# feather-v2_0.net
KiCad netlist of a schematic drawn in EAGLE
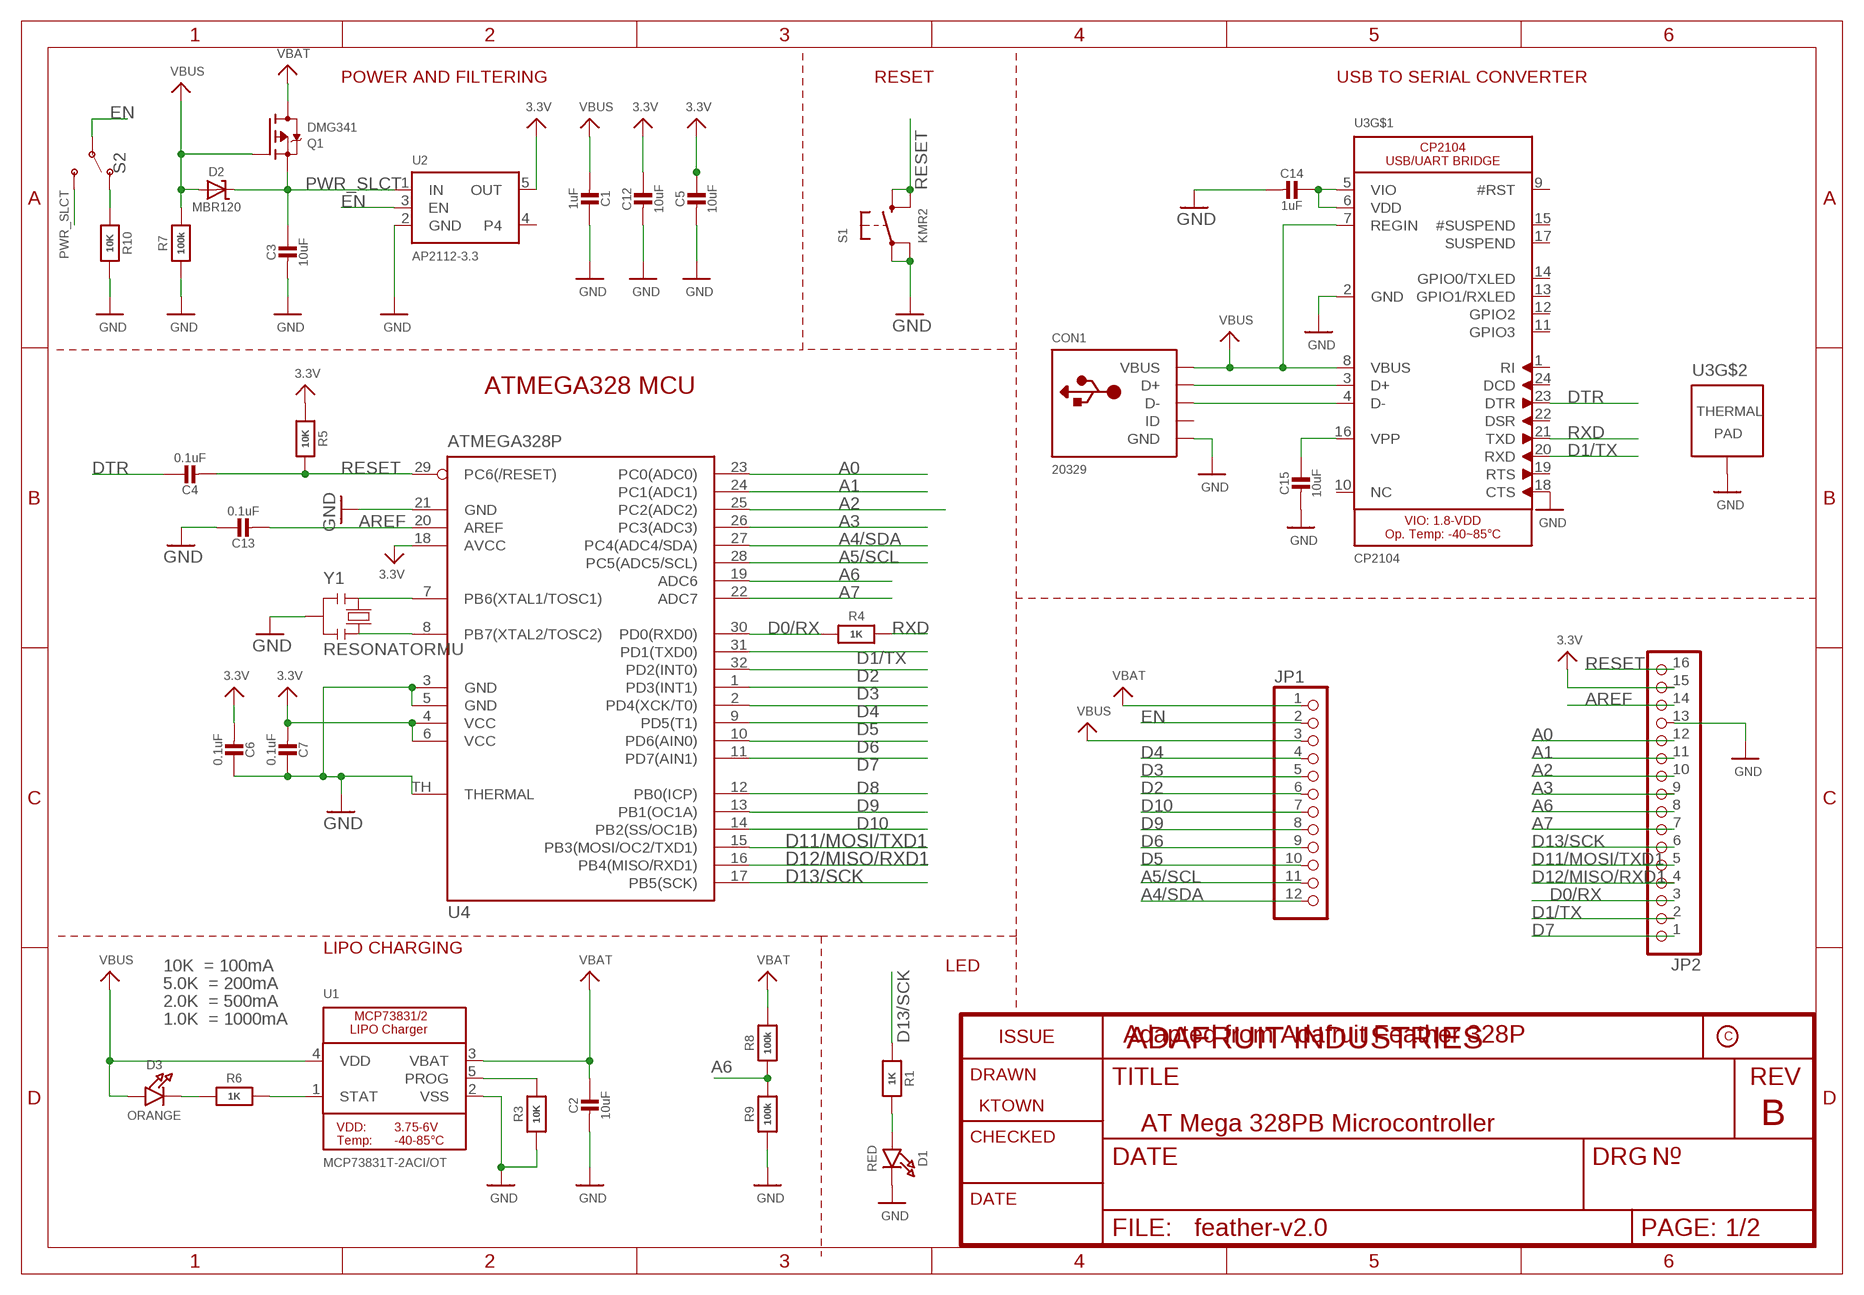
[diagram p0: schematic, sheet 1]
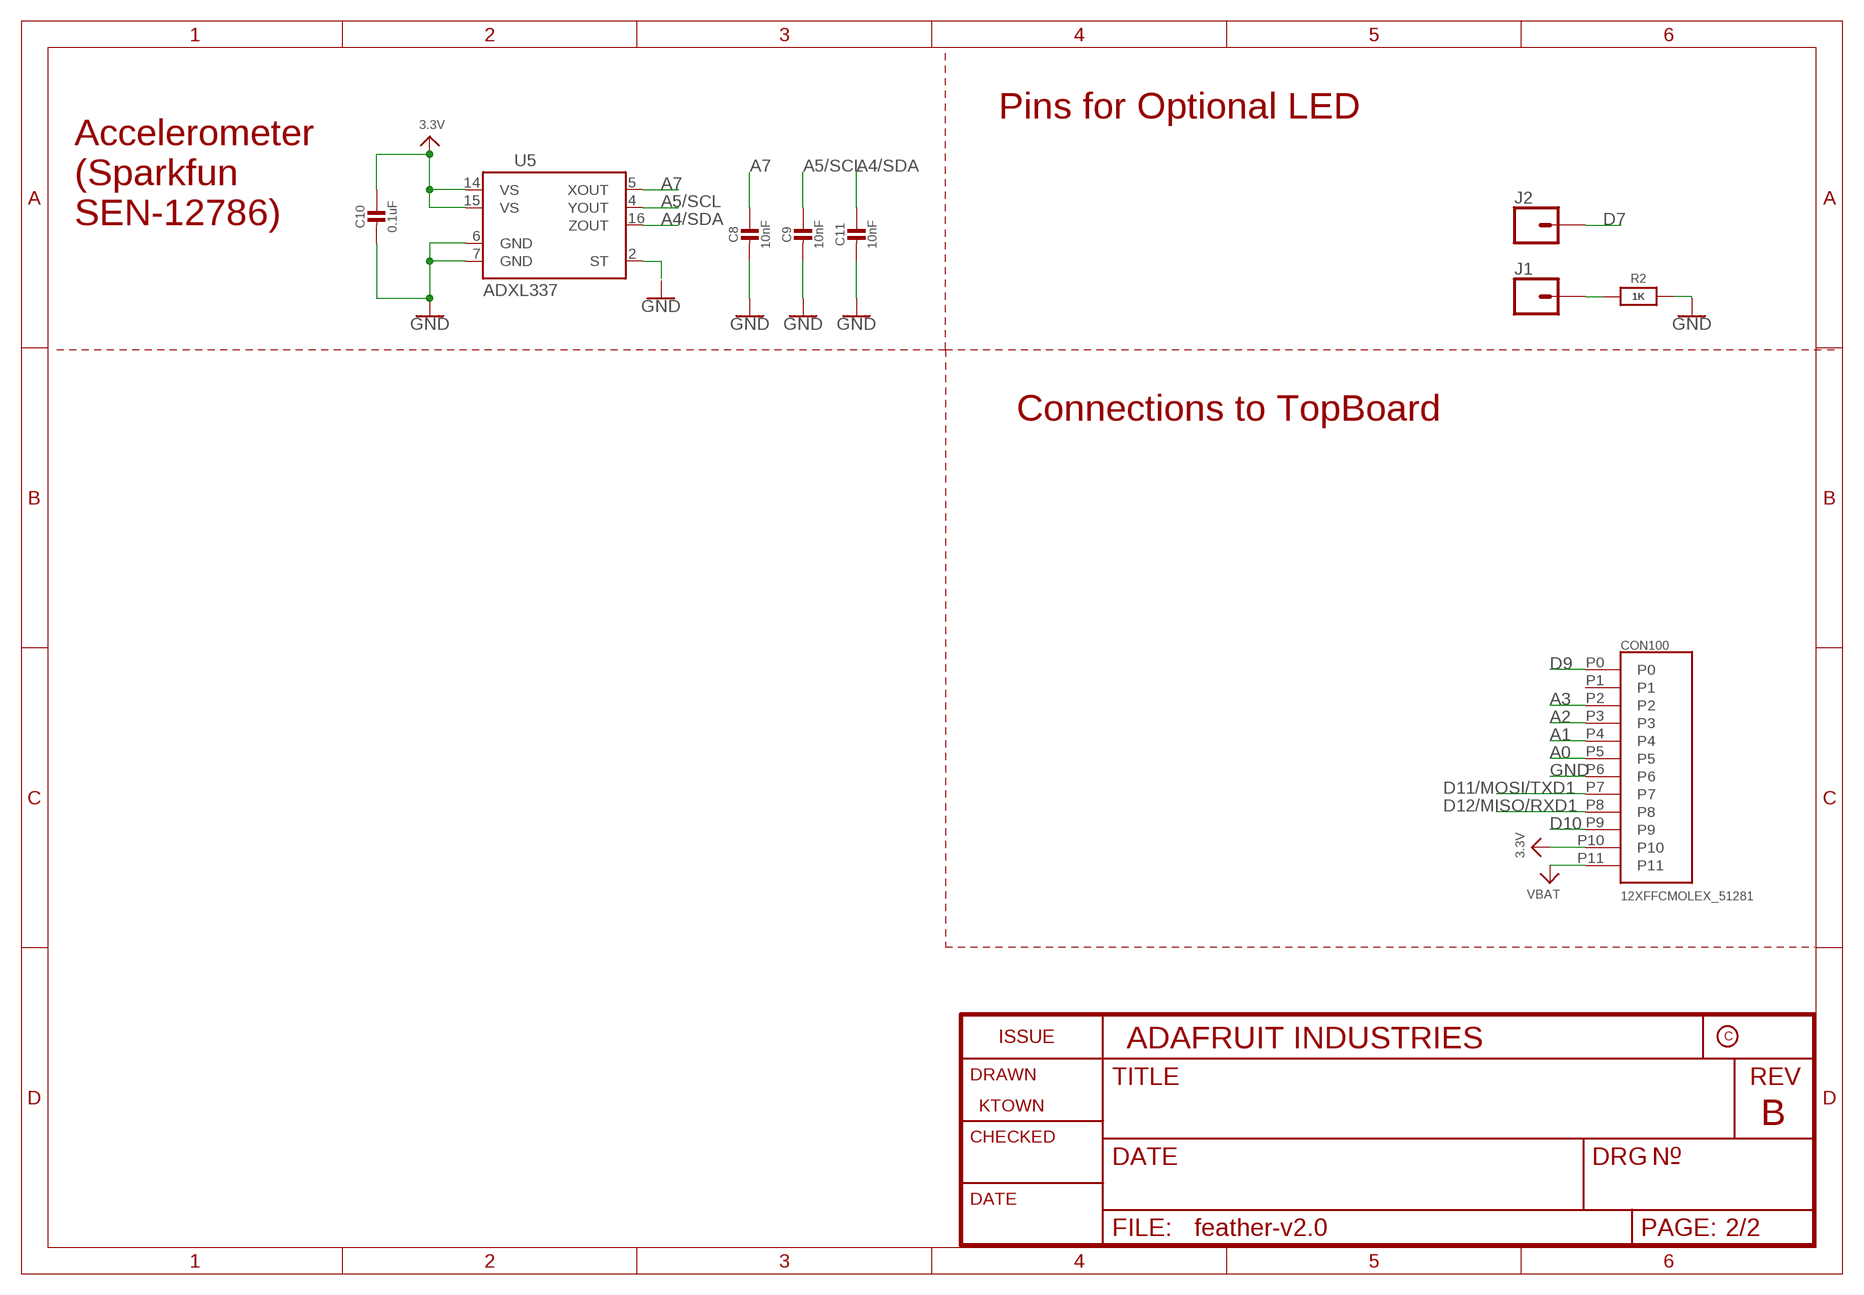
[diagram p1: schematic, sheet 2]

(export (version "E")
  (design (tool "Eeschema 10.0.6"))
  (components
    (comp (ref "C8")
      (value "10nF")
      (footprint "eagle-import:_0603MP")
      (libsource (lib "eagle-import") (part "CAP_CERAMIC_0603MP"))
    )
    (comp (ref "C9")
      (value "10nF")
      (footprint "eagle-import:_0603MP")
      (libsource (lib "eagle-import") (part "CAP_CERAMIC_0603MP"))
    )
    (comp (ref "C10")
      (value "0.1uF")
      (footprint "eagle-import:_0603MP")
      (libsource (lib "eagle-import") (part "CAP_CERAMIC_0603MP"))
    )
    (comp (ref "C11")
      (value "10nF")
      (footprint "eagle-import:_0603MP")
      (libsource (lib "eagle-import") (part "CAP_CERAMIC_0603MP"))
    )
    (comp (ref "CON100")
      (value "12XFFCMOLEX_51281")
      (footprint "eagle-import:MOLEX_51281-1294")
      (libsource (lib "eagle-import") (part "12XFFCMOLEX_51281"))
    )
    (comp (ref "J1")
      (value "CONN_01PTH_NO_SILK_YES_STOP")
      (footprint "eagle-import:1X01_NO_SILK")
      (libsource (lib "eagle-import") (part "CONN_01PTH_NO_SILK_YES_STOP"))
    )
    (comp (ref "J2")
      (value "CONN_01PTH_NO_SILK_YES_STOP")
      (footprint "eagle-import:1X01_NO_SILK")
      (libsource (lib "eagle-import") (part "CONN_01PTH_NO_SILK_YES_STOP"))
    )
    (comp (ref "R2")
      (value "1K")
      (footprint "eagle-import:_0603MP")
      (libsource (lib "eagle-import") (part "RESISTOR_0603MP"))
    )
    (comp (ref "U5")
      (value "ADXL337")
      (footprint "eagle-import:LFCSP_LQ-16")
      (libsource (lib "eagle-import") (part "ADXL337"))
    )
    (comp (ref "C1")
      (value "1uF")
      (footprint "eagle-import:_0603MP")
      (libsource (lib "eagle-import") (part "CAP_CERAMIC_0603MP"))
    )
    (comp (ref "C2")
      (value "10uF")
      (footprint "eagle-import:_0603MP")
      (libsource (lib "eagle-import") (part "CAP_CERAMIC_0603MP"))
    )
    (comp (ref "C3")
      (value "10uF")
      (footprint "eagle-import:_0603MP")
      (libsource (lib "eagle-import") (part "CAP_CERAMIC_0603MP"))
    )
    (comp (ref "C4")
      (value "0.1uF")
      (footprint "eagle-import:_0603MP")
      (libsource (lib "eagle-import") (part "CAP_CERAMIC_0603MP"))
    )
    (comp (ref "C5")
      (value "10uF")
      (footprint "eagle-import:_0603MP")
      (libsource (lib "eagle-import") (part "CAP_CERAMIC_0603MP"))
    )
    (comp (ref "C6")
      (value "0.1uF")
      (footprint "eagle-import:_0603MP")
      (libsource (lib "eagle-import") (part "CAP_CERAMIC_0603MP"))
    )
    (comp (ref "C7")
      (value "0.1uF")
      (footprint "eagle-import:_0603MP")
      (libsource (lib "eagle-import") (part "CAP_CERAMIC_0603MP"))
    )
    (comp (ref "C12")
      (value "10uF")
      (footprint "eagle-import:_0603MP")
      (libsource (lib "eagle-import") (part "CAP_CERAMIC_0603MP"))
    )
    (comp (ref "C13")
      (value "0.1uF")
      (footprint "eagle-import:_0603MP")
      (libsource (lib "eagle-import") (part "CAP_CERAMIC_0603MP"))
    )
    (comp (ref "C14")
      (value "1uF")
      (footprint "eagle-import:_0603MP")
      (libsource (lib "eagle-import") (part "CAP_CERAMIC_0603MP"))
    )
    (comp (ref "C15")
      (value "10uF")
      (footprint "eagle-import:_0603MP")
      (libsource (lib "eagle-import") (part "CAP_CERAMIC_0603MP"))
    )
    (comp (ref "CON1")
      (value "20329")
      (footprint "eagle-import:4UCONN_20329_V2")
      (libsource (lib "eagle-import") (part "USB_MICRO_20329_V2"))
    )
    (comp (ref "D1")
      (value "RED")
      (footprint "eagle-import:CHIPLED_0603_NOOUTLINE")
      (libsource (lib "eagle-import") (part "LED0603_NOOUTLINE"))
    )
    (comp (ref "D2")
      (value "MBR120")
      (footprint "eagle-import:SOD-323")
      (libsource (lib "eagle-import") (part "DIODE-SCHOTTKYSOD-323"))
    )
    (comp (ref "D3")
      (value "ORANGE")
      (footprint "eagle-import:CHIPLED_0603_NOOUTLINE")
      (libsource (lib "eagle-import") (part "LED0603_NOOUTLINE"))
    )
    (comp (ref "JP1")
      (value "HEADER-1X12")
      (footprint "eagle-import:1X12_ROUND")
      (libsource (lib "eagle-import") (part "HEADER-1X12"))
    )
    (comp (ref "JP2")
      (value "HEADER-1X16ROUND")
      (footprint "eagle-import:1X16_ROUND")
      (libsource (lib "eagle-import") (part "HEADER-1X16ROUND"))
    )
    (comp (ref "Q1")
      (value "DMG341")
      (footprint "eagle-import:SOT23-R")
      (libsource (lib "eagle-import") (part "MOSFET-P"))
    )
    (comp (ref "R1")
      (value "1K")
      (footprint "eagle-import:_0603MP")
      (libsource (lib "eagle-import") (part "RESISTOR_0603MP"))
    )
    (comp (ref "R3")
      (value "10K")
      (footprint "eagle-import:_0603MP")
      (libsource (lib "eagle-import") (part "RESISTOR_0603MP"))
    )
    (comp (ref "R4")
      (value "1K")
      (footprint "eagle-import:_0603MP")
      (libsource (lib "eagle-import") (part "RESISTOR_0603MP"))
    )
    (comp (ref "R5")
      (value "10K")
      (footprint "eagle-import:_0603MP")
      (libsource (lib "eagle-import") (part "RESISTOR_0603MP"))
    )
    (comp (ref "R6")
      (value "1K")
      (footprint "eagle-import:_0603MP")
      (libsource (lib "eagle-import") (part "RESISTOR_0603MP"))
    )
    (comp (ref "R7")
      (value "100k")
      (footprint "eagle-import:_0603MP")
      (libsource (lib "eagle-import") (part "RESISTOR_0603MP"))
    )
    (comp (ref "R8")
      (value "100k")
      (footprint "eagle-import:_0603MP")
      (libsource (lib "eagle-import") (part "RESISTOR_0603MP"))
    )
    (comp (ref "R9")
      (value "100k")
      (footprint "eagle-import:_0603MP")
      (libsource (lib "eagle-import") (part "RESISTOR_0603MP"))
    )
    (comp (ref "R10")
      (value "10K")
      (footprint "eagle-import:_0603MP")
      (libsource (lib "eagle-import") (part "RESISTOR_0603MP"))
    )
    (comp (ref "S1")
      (value "KMR2")
      (footprint "eagle-import:BTN_KMR2_4.6X2.8")
      (libsource (lib "eagle-import") (part "SWITCH_TACT_SMT4.6X2.8"))
    )
    (comp (ref "S2")
      (value "SWITCH-SPDT-SMD-RIGHT-ANGLE")
      (footprint "eagle-import:SWITCH_SPST_SMD_A")
      (libsource (lib "eagle-import") (part "SWITCH-SPDT-SMD-RIGHT-ANGLE"))
    )
    (comp (ref "U1")
      (value "MCP73831T-2ACI/OT")
      (footprint "eagle-import:SOT23-5")
      (libsource (lib "eagle-import") (part "MCP73831/2"))
    )
    (comp (ref "U2")
      (value "AP2112-3.3")
      (footprint "eagle-import:SOT23-5")
      (libsource (lib "eagle-import") (part "VREG_SOT23-5"))
    )
    (comp (ref "U3")
      (value "CP2104")
      (footprint "eagle-import:QFN24_4MM_SMSC")
      (libsource (lib "eagle-import") (part "CP2104"))
    )
    (comp (ref "U4")
      (value "ATMEGA328P")
      (footprint "eagle-import:MLF32-TH")
      (fields (field (name "MF") "MicroChip") (field (name "MPN") "ATMEGA328PB-MU"))
      (libsource (lib "eagle-import") (part "MEGA328PB"))
    )
    (comp (ref "Y1")
      (value "RESONATORMU")
      (footprint "eagle-import:RESONATOR")
      (libsource (lib "eagle-import") (part "RESONATORMU"))
    )
  )
  (nets
    (net (code "1") (name "3.3V") (class "Default")
      (node (ref "C10") (pin "1") (pinfunction "1_1") (pintype "passive"))
      (node (ref "C12") (pin "1") (pinfunction "1_1") (pintype "passive"))
      (node (ref "C5") (pin "1") (pinfunction "1_1") (pintype "passive"))
      (node (ref "C6") (pin "2") (pinfunction "2_2") (pintype "passive"))
      (node (ref "C7") (pin "2") (pinfunction "2_2") (pintype "passive"))
      (node (ref "CON100") (pin "P10") (pinfunction "P10_P10") (pintype "bidirectional"))
      (node (ref "JP2") (pin "15") (pinfunction "15_15") (pintype "passive"))
      (node (ref "R5") (pin "2") (pinfunction "2_2") (pintype "passive"))
      (node (ref "U2") (pin "5") (pinfunction "OUT_5") (pintype "power_in"))
      (node (ref "U4") (pin "18") (pinfunction "AVCC_18") (pintype "power_in"))
      (node (ref "U4") (pin "4") (pinfunction "VCC_4") (pintype "power_in"))
      (node (ref "U4") (pin "6") (pinfunction "VCC_6") (pintype "power_in"))
      (node (ref "U5") (pin "14") (pinfunction "VS_14") (pintype "bidirectional"))
      (node (ref "U5") (pin "15") (pinfunction "VS_15") (pintype "bidirectional"))
    )
    (net (code "2") (name "A0") (class "Default")
      (node (ref "CON100") (pin "P5") (pinfunction "P5_P5") (pintype "bidirectional"))
      (node (ref "JP2") (pin "12") (pinfunction "12_12") (pintype "passive"))
      (node (ref "U4") (pin "23") (pinfunction "PC0(ADC0)_23") (pintype "bidirectional"))
    )
    (net (code "3") (name "A1") (class "Default")
      (node (ref "CON100") (pin "P4") (pinfunction "P4_P4") (pintype "bidirectional"))
      (node (ref "JP2") (pin "11") (pinfunction "11_11") (pintype "passive"))
      (node (ref "U4") (pin "24") (pinfunction "PC1(ADC1)_24") (pintype "bidirectional"))
    )
    (net (code "4") (name "A2") (class "Default")
      (node (ref "CON100") (pin "P3") (pinfunction "P3_P3") (pintype "bidirectional"))
      (node (ref "JP2") (pin "10") (pinfunction "10_10") (pintype "passive"))
      (node (ref "U4") (pin "25") (pinfunction "PC2(ADC2)_25") (pintype "bidirectional"))
    )
    (net (code "5") (name "A3") (class "Default")
      (node (ref "CON100") (pin "P2") (pinfunction "P2_P2") (pintype "bidirectional"))
      (node (ref "JP2") (pin "9") (pinfunction "9_9") (pintype "passive"))
      (node (ref "U4") (pin "26") (pinfunction "PC3(ADC3)_26") (pintype "bidirectional"))
    )
    (net (code "6") (name "A4{slash}SDA") (class "Default")
      (node (ref "C11") (pin "1") (pinfunction "1_1") (pintype "passive"))
      (node (ref "JP1") (pin "12") (pinfunction "12_12") (pintype "passive"))
      (node (ref "U4") (pin "27") (pinfunction "PC4(ADC4/SDA)_27") (pintype "bidirectional"))
      (node (ref "U5") (pin "16") (pinfunction "ZOUT_16") (pintype "bidirectional"))
    )
    (net (code "7") (name "A5{slash}SCL") (class "Default")
      (node (ref "C9") (pin "1") (pinfunction "1_1") (pintype "passive"))
      (node (ref "JP1") (pin "11") (pinfunction "11_11") (pintype "passive"))
      (node (ref "U4") (pin "28") (pinfunction "PC5(ADC5/SCL)_28") (pintype "bidirectional"))
      (node (ref "U5") (pin "4") (pinfunction "YOUT_4") (pintype "bidirectional"))
    )
    (net (code "8") (name "A6") (class "Default")
      (node (ref "JP2") (pin "8") (pinfunction "8_8") (pintype "passive"))
      (node (ref "R8") (pin "1") (pinfunction "1_1") (pintype "passive"))
      (node (ref "R9") (pin "2") (pinfunction "2_2") (pintype "passive"))
      (node (ref "U4") (pin "19") (pinfunction "ADC6_19") (pintype "bidirectional"))
    )
    (net (code "9") (name "A7") (class "Default")
      (node (ref "C8") (pin "1") (pinfunction "1_1") (pintype "passive"))
      (node (ref "JP2") (pin "7") (pinfunction "7_7") (pintype "passive"))
      (node (ref "U4") (pin "22") (pinfunction "ADC7_22") (pintype "bidirectional"))
      (node (ref "U5") (pin "5") (pinfunction "XOUT_5") (pintype "bidirectional"))
    )
    (net (code "10") (name "AREF") (class "Default")
      (node (ref "C13") (pin "2") (pinfunction "2_2") (pintype "passive"))
      (node (ref "JP2") (pin "14") (pinfunction "14_14") (pintype "passive"))
      (node (ref "U4") (pin "20") (pinfunction "AREF_20") (pintype "passive"))
    )
    (net (code "11") (name "D0{slash}RX") (class "Default")
      (node (ref "JP2") (pin "3") (pinfunction "3_3") (pintype "passive"))
      (node (ref "R4") (pin "1") (pinfunction "1_1") (pintype "passive"))
      (node (ref "U4") (pin "30") (pinfunction "PD0(RXD0)_30") (pintype "bidirectional"))
    )
    (net (code "12") (name "D1{slash}TX") (class "Default")
      (node (ref "JP2") (pin "2") (pinfunction "2_2") (pintype "passive"))
      (node (ref "U3") (pin "20") (pinfunction "RXD_20") (pintype "input"))
      (node (ref "U4") (pin "31") (pinfunction "PD1(TXD0)_31") (pintype "bidirectional"))
    )
    (net (code "13") (name "D2") (class "Default")
      (node (ref "JP1") (pin "6") (pinfunction "6_6") (pintype "passive"))
      (node (ref "U4") (pin "32") (pinfunction "PD2(INT0)_32") (pintype "bidirectional"))
    )
    (net (code "14") (name "D3") (class "Default")
      (node (ref "JP1") (pin "5") (pinfunction "5_5") (pintype "passive"))
      (node (ref "U4") (pin "1") (pinfunction "PD3(INT1)_1") (pintype "bidirectional"))
    )
    (net (code "15") (name "D4") (class "Default")
      (node (ref "JP1") (pin "4") (pinfunction "4_4") (pintype "passive"))
      (node (ref "U4") (pin "2") (pinfunction "PD4(XCK/T0)_2") (pintype "bidirectional"))
    )
    (net (code "16") (name "D5") (class "Default")
      (node (ref "JP1") (pin "10") (pinfunction "10_10") (pintype "passive"))
      (node (ref "U4") (pin "9") (pinfunction "PD5(T1)_9") (pintype "bidirectional"))
    )
    (net (code "17") (name "D6") (class "Default")
      (node (ref "JP1") (pin "9") (pinfunction "9_9") (pintype "passive"))
      (node (ref "U4") (pin "10") (pinfunction "PD6(AIN0)_10") (pintype "bidirectional"))
    )
    (net (code "18") (name "D7") (class "Default")
      (node (ref "J2") (pin "1") (pinfunction "1_1") (pintype "passive"))
      (node (ref "JP2") (pin "1") (pinfunction "1_1") (pintype "passive"))
      (node (ref "U4") (pin "11") (pinfunction "PD7(AIN1)_11") (pintype "bidirectional"))
    )
    (net (code "19") (name "D8") (class "Default")
      (node (ref "U4") (pin "12") (pinfunction "PB0(ICP)_12") (pintype "bidirectional"))
    )
    (net (code "20") (name "D9") (class "Default")
      (node (ref "CON100") (pin "P0") (pinfunction "P0_P0") (pintype "bidirectional"))
      (node (ref "JP1") (pin "8") (pinfunction "8_8") (pintype "passive"))
      (node (ref "U4") (pin "13") (pinfunction "PB1(OC1A)_13") (pintype "bidirectional"))
    )
    (net (code "21") (name "D10") (class "Default")
      (node (ref "CON100") (pin "P9") (pinfunction "P9_P9") (pintype "bidirectional"))
      (node (ref "JP1") (pin "7") (pinfunction "7_7") (pintype "passive"))
      (node (ref "U4") (pin "14") (pinfunction "PB2(SS/OC1B)_14") (pintype "bidirectional"))
    )
    (net (code "22") (name "D11{slash}MOSI{slash}TXD1") (class "Default")
      (node (ref "CON100") (pin "P7") (pinfunction "P7_P7") (pintype "bidirectional"))
      (node (ref "JP2") (pin "5") (pinfunction "5_5") (pintype "passive"))
      (node (ref "U4") (pin "15") (pinfunction "PB3(MOSI/OC2/TXD1)_15") (pintype "bidirectional"))
    )
    (net (code "23") (name "D12{slash}MISO{slash}RXD1") (class "Default")
      (node (ref "CON100") (pin "P8") (pinfunction "P8_P8") (pintype "bidirectional"))
      (node (ref "JP2") (pin "4") (pinfunction "4_4") (pintype "passive"))
      (node (ref "U4") (pin "16") (pinfunction "PB4(MISO/RXD1)_16") (pintype "bidirectional"))
    )
    (net (code "24") (name "D13{slash}SCK") (class "Default")
      (node (ref "JP2") (pin "6") (pinfunction "6_6") (pintype "passive"))
      (node (ref "R1") (pin "1") (pinfunction "1_1") (pintype "passive"))
      (node (ref "U4") (pin "17") (pinfunction "PB5(SCK)_17") (pintype "bidirectional"))
    )
    (net (code "25") (name "DTR") (class "Default")
      (node (ref "C4") (pin "1") (pinfunction "1_1") (pintype "passive"))
      (node (ref "U3") (pin "23") (pinfunction "DTR_23") (pintype "output"))
    )
    (net (code "26") (name "EN") (class "Default")
      (node (ref "JP1") (pin "2") (pinfunction "2_2") (pintype "passive"))
      (node (ref "S2") (pin "2") (pinfunction "P_2") (pintype "passive"))
      (node (ref "U2") (pin "3") (pinfunction "EN_3") (pintype "input"))
    )
    (net (code "27") (name "GND") (class "Default")
      (node (ref "C1") (pin "1") (pinfunction "1_1") (pintype "passive"))
      (node (ref "C10") (pin "2") (pinfunction "2_2") (pintype "passive"))
      (node (ref "C11") (pin "2") (pinfunction "2_2") (pintype "passive"))
      (node (ref "C12") (pin "2") (pinfunction "2_2") (pintype "passive"))
      (node (ref "C13") (pin "1") (pinfunction "1_1") (pintype "passive"))
      (node (ref "C14") (pin "2") (pinfunction "2_2") (pintype "passive"))
      (node (ref "C15") (pin "2") (pinfunction "2_2") (pintype "passive"))
      (node (ref "C2") (pin "2") (pinfunction "2_2") (pintype "passive"))
      (node (ref "C3") (pin "2") (pinfunction "2_2") (pintype "passive"))
      (node (ref "C5") (pin "2") (pinfunction "2_2") (pintype "passive"))
      (node (ref "C6") (pin "1") (pinfunction "1_1") (pintype "passive"))
      (node (ref "C7") (pin "1") (pinfunction "1_1") (pintype "passive"))
      (node (ref "C8") (pin "2") (pinfunction "2_2") (pintype "passive"))
      (node (ref "C9") (pin "2") (pinfunction "2_2") (pintype "passive"))
      (node (ref "CON1") (pin "BASE@1") (pinfunction "GND_BASE@1") (pintype "power_in"))
      (node (ref "CON1") (pin "BASE@2") (pinfunction "GND_BASE@2") (pintype "power_in"))
      (node (ref "CON1") (pin "GND") (pinfunction "GND_GND") (pintype "power_in"))
      (node (ref "CON1") (pin "SPRT@1") (pinfunction "GND_SPRT@1") (pintype "power_in"))
      (node (ref "CON1") (pin "SPRT@2") (pinfunction "GND_SPRT@2") (pintype "power_in"))
      (node (ref "CON1") (pin "SPRT@3") (pinfunction "GND_SPRT@3") (pintype "power_in"))
      (node (ref "CON1") (pin "SPRT@4") (pinfunction "GND_SPRT@4") (pintype "power_in"))
      (node (ref "CON100") (pin "P6") (pinfunction "P6_P6") (pintype "bidirectional"))
      (node (ref "D1") (pin "C") (pinfunction "C_C") (pintype "passive"))
      (node (ref "JP2") (pin "13") (pinfunction "13_13") (pintype "passive"))
      (node (ref "R10") (pin "1") (pinfunction "1_1") (pintype "passive"))
      (node (ref "R2") (pin "2") (pinfunction "2_2") (pintype "passive"))
      (node (ref "R3") (pin "1") (pinfunction "1_1") (pintype "passive"))
      (node (ref "R7") (pin "1") (pinfunction "1_1") (pintype "passive"))
      (node (ref "R9") (pin "1") (pinfunction "1_1") (pintype "passive"))
      (node (ref "S1") (pin "A") (pinfunction "P_A") (pintype "passive"))
      (node (ref "S1") (pin "A'") (pinfunction "P1_A'") (pintype "passive"))
      (node (ref "U1") (pin "2") (pinfunction "VSS_2") (pintype "power_in"))
      (node (ref "U2") (pin "2") (pinfunction "GND_2") (pintype "power_in"))
      (node (ref "U3") (pin "18") (pinfunction "CTS_18") (pintype "input"))
      (node (ref "U3") (pin "2") (pinfunction "GND_2") (pintype "power_in"))
      (node (ref "U3") (pin "THERM") (pinfunction "TP_THERM") (pintype "power_in"))
      (node (ref "U4") (pin "21") (pinfunction "GND_21") (pintype "power_in"))
      (node (ref "U4") (pin "3") (pinfunction "GND_3") (pintype "power_in"))
      (node (ref "U4") (pin "5") (pinfunction "GND_5") (pintype "power_in"))
      (node (ref "U4") (pin "TH") (pinfunction "THERMAL_TH") (pintype "passive"))
      (node (ref "U5") (pin "6") (pinfunction "GND_6") (pintype "bidirectional"))
      (node (ref "U5") (pin "7") (pinfunction "GND_7") (pintype "bidirectional"))
      (node (ref "Y1") (pin "2") (pinfunction "2_2") (pintype "passive"))
    )
    (net (code "28") (name "Net-(D1-PadA)") (class "Default")
      (node (ref "D1") (pin "A") (pinfunction "A_A") (pintype "passive"))
      (node (ref "R1") (pin "2") (pinfunction "2_2") (pintype "passive"))
    )
    (net (code "29") (name "Net-(D3-PadC)") (class "Default")
      (node (ref "D3") (pin "C") (pinfunction "C_C") (pintype "passive"))
      (node (ref "R6") (pin "1") (pinfunction "1_1") (pintype "passive"))
    )
    (net (code "30") (name "Net-(J1-Pad1)") (class "Default")
      (node (ref "J1") (pin "1") (pinfunction "1_1") (pintype "passive"))
      (node (ref "R2") (pin "1") (pinfunction "1_1") (pintype "passive"))
    )
    (net (code "31") (name "Net-(S2-O)") (class "Default")
      (node (ref "R10") (pin "2") (pinfunction "2_2") (pintype "passive"))
      (node (ref "S2") (pin "1") (pinfunction "O_1") (pintype "passive"))
    )
    (net (code "32") (name "Net-(U1-PROG)") (class "Default")
      (node (ref "R3") (pin "2") (pinfunction "2_2") (pintype "passive"))
      (node (ref "U1") (pin "5") (pinfunction "PROG_5") (pintype "input"))
    )
    (net (code "33") (name "Net-(U1-STAT)") (class "Default")
      (node (ref "R6") (pin "2") (pinfunction "2_2") (pintype "passive"))
      (node (ref "U1") (pin "1") (pinfunction "STAT_1") (pintype "output"))
    )
    (net (code "34") (name "Net-(U3A-D+)") (class "Default")
      (node (ref "CON1") (pin "D+") (pinfunction "D+_D+") (pintype "bidirectional"))
      (node (ref "U3") (pin "3") (pinfunction "D+_3") (pintype "bidirectional"))
    )
    (net (code "35") (name "Net-(U3A-D-)") (class "Default")
      (node (ref "CON1") (pin "D-") (pinfunction "D-_D-") (pintype "bidirectional"))
      (node (ref "U3") (pin "4") (pinfunction "D-_4") (pintype "bidirectional"))
    )
    (net (code "36") (name "Net-(U3A-VDD)") (class "Default")
      (node (ref "C14") (pin "1") (pinfunction "1_1") (pintype "passive"))
      (node (ref "U3") (pin "5") (pinfunction "VIO_5") (pintype "power_in"))
      (node (ref "U3") (pin "6") (pinfunction "VDD_6") (pintype "power_in"))
    )
    (net (code "37") (name "Net-(U3A-VPP)") (class "Default")
      (node (ref "C15") (pin "1") (pinfunction "1_1") (pintype "passive"))
      (node (ref "U3") (pin "16") (pinfunction "VPP_16") (pintype "bidirectional"))
    )
    (net (code "38") (name "Net-(U4-PB6(XTAL1{slash}TOSC1))") (class "Default")
      (node (ref "U4") (pin "7") (pinfunction "PB6(XTAL1/TOSC1)_7") (pintype "bidirectional"))
      (node (ref "Y1") (pin "1") (pinfunction "1_1") (pintype "passive"))
    )
    (net (code "39") (name "Net-(U4-PB7(XTAL2{slash}TOSC2))") (class "Default")
      (node (ref "U4") (pin "8") (pinfunction "PB7(XTAL2/TOSC2)_8") (pintype "bidirectional"))
      (node (ref "Y1") (pin "3") (pinfunction "3_3") (pintype "passive"))
    )
    (net (code "40") (name "PWR_SLCT") (class "Default")
      (node (ref "C3") (pin "1") (pinfunction "1_1") (pintype "passive"))
      (node (ref "D2") (pin "C") (pinfunction "C_C") (pintype "passive"))
      (node (ref "Q1") (pin "2") (pinfunction "S_2") (pintype "passive"))
      (node (ref "S2") (pin "3") (pinfunction "S_3") (pintype "passive"))
      (node (ref "U2") (pin "1") (pinfunction "IN_1") (pintype "power_in"))
    )
    (net (code "41") (name "RESET") (class "Default")
      (node (ref "C4") (pin "2") (pinfunction "2_2") (pintype "passive"))
      (node (ref "JP2") (pin "16") (pinfunction "16_16") (pintype "passive"))
      (node (ref "R5") (pin "1") (pinfunction "1_1") (pintype "passive"))
      (node (ref "S1") (pin "B") (pinfunction "S_B") (pintype "passive"))
      (node (ref "S1") (pin "B'") (pinfunction "S1_B'") (pintype "passive"))
      (node (ref "U4") (pin "29") (pinfunction "PC6(/RESET)_29") (pintype "bidirectional"))
    )
    (net (code "42") (name "RXD") (class "Default")
      (node (ref "R4") (pin "2") (pinfunction "2_2") (pintype "passive"))
      (node (ref "U3") (pin "21") (pinfunction "TXD_21") (pintype "output"))
    )
    (net (code "43") (name "VBAT") (class "Default")
      (node (ref "C2") (pin "1") (pinfunction "1_1") (pintype "passive"))
      (node (ref "CON100") (pin "P11") (pinfunction "P11_P11") (pintype "bidirectional"))
      (node (ref "JP1") (pin "1") (pinfunction "1_1") (pintype "passive"))
      (node (ref "Q1") (pin "3") (pinfunction "D_3") (pintype "passive"))
      (node (ref "R8") (pin "2") (pinfunction "2_2") (pintype "passive"))
      (node (ref "U1") (pin "3") (pinfunction "VBAT_3") (pintype "power_in"))
    )
    (net (code "44") (name "VBUS") (class "Default")
      (node (ref "C1") (pin "2") (pinfunction "2_2") (pintype "passive"))
      (node (ref "CON1") (pin "VBUS") (pinfunction "VBUS_VBUS") (pintype "power_in"))
      (node (ref "D2") (pin "A") (pinfunction "A_A") (pintype "passive"))
      (node (ref "D3") (pin "A") (pinfunction "A_A") (pintype "passive"))
      (node (ref "JP1") (pin "3") (pinfunction "3_3") (pintype "passive"))
      (node (ref "Q1") (pin "1") (pinfunction "G_1") (pintype "passive"))
      (node (ref "R7") (pin "2") (pinfunction "2_2") (pintype "passive"))
      (node (ref "U1") (pin "4") (pinfunction "VDD_4") (pintype "power_in"))
      (node (ref "U3") (pin "7") (pinfunction "REGIN_7") (pintype "power_in"))
      (node (ref "U3") (pin "8") (pinfunction "VBUS_8") (pintype "power_in"))
    )
    (net (code "45") (name "unconnected-(CON1-PadID)") (class "Default")
      (node (ref "CON1") (pin "ID") (pinfunction "ID_ID") (pintype "bidirectional"))
    )
    (net (code "46") (name "unconnected-(CON100-PadP1)") (class "Default")
      (node (ref "CON100") (pin "P1") (pinfunction "P1_P1") (pintype "bidirectional"))
    )
    (net (code "47") (name "unconnected-(U2-P4-Pad4)") (class "Default")
      (node (ref "U2") (pin "4") (pinfunction "P4_4") (pintype "bidirectional"))
    )
    (net (code "48") (name "unconnected-(U3A-#RST-Pad9)") (class "Default")
      (node (ref "U3") (pin "9") (pinfunction "#RST_9") (pintype "bidirectional"))
    )
    (net (code "49") (name "unconnected-(U3A-#SUSPEND-Pad15)") (class "Default")
      (node (ref "U3") (pin "15") (pinfunction "#SUSPEND_15") (pintype "output"))
    )
    (net (code "50") (name "unconnected-(U3A-DCD-Pad24)") (class "Default")
      (node (ref "U3") (pin "24") (pinfunction "DCD_24") (pintype "input"))
    )
    (net (code "51") (name "unconnected-(U3A-DSR-Pad22)") (class "Default")
      (node (ref "U3") (pin "22") (pinfunction "DSR_22") (pintype "input"))
    )
    (net (code "52") (name "unconnected-(U3A-GPIO0{slash}TXLED-Pad14)") (class "Default")
      (node (ref "U3") (pin "14") (pinfunction "GPIO0/TXLED_14") (pintype "bidirectional"))
    )
    (net (code "53") (name "unconnected-(U3A-GPIO1{slash}RXLED-Pad13)") (class "Default")
      (node (ref "U3") (pin "13") (pinfunction "GPIO1/RXLED_13") (pintype "bidirectional"))
    )
    (net (code "54") (name "unconnected-(U3A-GPIO2-Pad12)") (class "Default")
      (node (ref "U3") (pin "12") (pinfunction "GPIO2_12") (pintype "bidirectional"))
    )
    (net (code "55") (name "unconnected-(U3A-GPIO3-Pad11)") (class "Default")
      (node (ref "U3") (pin "11") (pinfunction "GPIO3_11") (pintype "bidirectional"))
    )
    (net (code "56") (name "unconnected-(U3A-NC-Pad10)") (class "Default")
      (node (ref "U3") (pin "10") (pinfunction "NC_10") (pintype "no_connect"))
    )
    (net (code "57") (name "unconnected-(U3A-RI-Pad1)") (class "Default")
      (node (ref "U3") (pin "1") (pinfunction "RI_1") (pintype "input"))
    )
    (net (code "58") (name "unconnected-(U3A-RTS-Pad19)") (class "Default")
      (node (ref "U3") (pin "19") (pinfunction "RTS_19") (pintype "output"))
    )
    (net (code "59") (name "unconnected-(U3A-SUSPEND-Pad17)") (class "Default")
      (node (ref "U3") (pin "17") (pinfunction "SUSPEND_17") (pintype "output"))
    )
    (net (code "60") (name "unconnected-(U5-ST-Pad2)") (class "Default")
      (node (ref "U5") (pin "2") (pinfunction "ST_2") (pintype "bidirectional"))
    )
  )
)
